# w6_hello.net
KiCad netlist of a schematic drawn in EAGLE
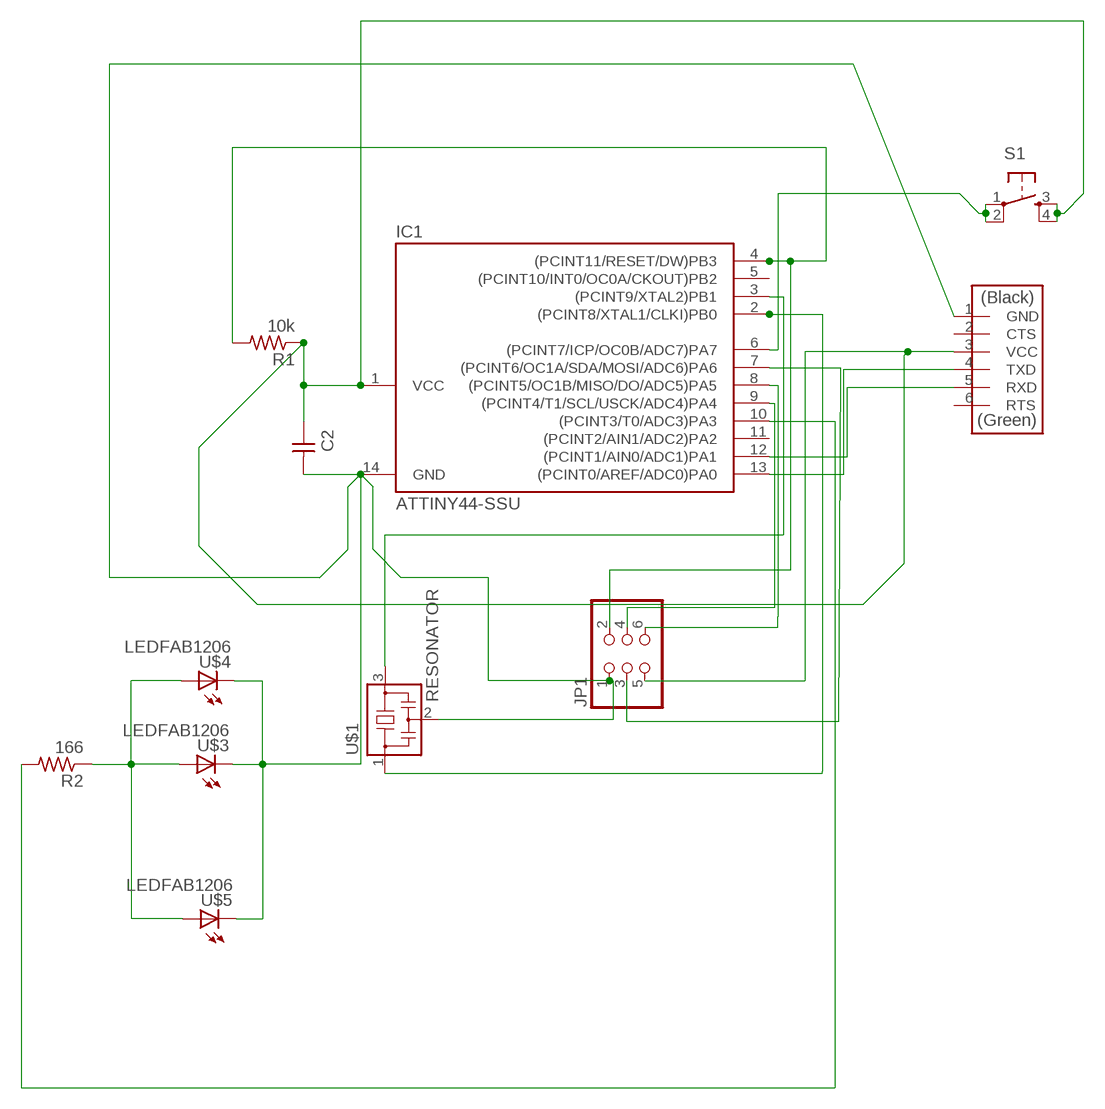
[diagram p0: schematic, sheet 1]

(export (version "E")
  (design (tool "Eeschema 10.0.6"))
  (components
    (comp (ref "C2")
      (value "CAP-UNPOLARIZEDFAB")
      (footprint "eagle-import:C1206FAB")
      (libsource (lib "eagle-import") (part "CAP-UNPOLARIZEDFAB"))
    )
    (comp (ref "IC1")
      (value "ATTINY44-SSU")
      (footprint "eagle-import:SOIC14")
      (libsource (lib "eagle-import") (part "ATTINY44-SSU"))
    )
    (comp (ref "JP1")
      (value "PINHD-2X3-SMD")
      (footprint "eagle-import:2X03SMD")
      (libsource (lib "eagle-import") (part "PINHD-2X3-SMD"))
    )
    (comp (ref "R1")
      (value "10k")
      (footprint "eagle-import:R1206")
      (libsource (lib "eagle-import") (part "RES-US1206"))
    )
    (comp (ref "R2")
      (value "166")
      (footprint "eagle-import:R1206")
      (libsource (lib "eagle-import") (part "RES-US1206"))
    )
    (comp (ref "S1")
      (value "6MM_SWITCH6MM_SWITCH")
      (footprint "eagle-import:6MM_SWITCH")
      (libsource (lib "eagle-import") (part "6MM_SWITCH6MM_SWITCH"))
    )
    (comp (ref "U$1")
      (value "RESONATOR")
      (footprint "eagle-import:EFOBM")
      (libsource (lib "eagle-import") (part "RESONATOR"))
    )
    (comp (ref "U$2")
      (value "FTDI-SMD-HEADER")
      (footprint "eagle-import:1X06SMD")
      (libsource (lib "eagle-import") (part "FTDI-SMD-HEADER"))
    )
    (comp (ref "U$3")
      (value "LEDFAB1206")
      (footprint "eagle-import:LED1206FAB")
      (libsource (lib "eagle-import") (part "LEDFAB1206"))
    )
    (comp (ref "U$4")
      (value "LEDFAB1206")
      (footprint "eagle-import:LED1206FAB")
      (libsource (lib "eagle-import") (part "LEDFAB1206"))
    )
    (comp (ref "U$5")
      (value "LEDFAB1206")
      (footprint "eagle-import:LED1206FAB")
      (libsource (lib "eagle-import") (part "LEDFAB1206"))
    )
  )
  (nets
    (net (code "1") (name "Net-(IC1-(PCINT0{slash}AREF{slash}ADC0)PA0)") (class "Default")
      (node (ref "IC1") (pin "13") (pinfunction "(PCINT0/AREF/ADC0)PA0_13") (pintype "bidirectional"))
      (node (ref "U$2") (pin "4") (pinfunction "TXD_4") (pintype "bidirectional"))
    )
    (net (code "2") (name "Net-(IC1-(PCINT1{slash}AIN0{slash}ADC1)PA1)") (class "Default")
      (node (ref "IC1") (pin "12") (pinfunction "(PCINT1/AIN0/ADC1)PA1_12") (pintype "bidirectional"))
      (node (ref "U$2") (pin "5") (pinfunction "RXD_5") (pintype "bidirectional"))
    )
    (net (code "3") (name "Net-(IC1-(PCINT3{slash}T0{slash}ADC3)PA3)") (class "Default")
      (node (ref "IC1") (pin "10") (pinfunction "(PCINT3/T0/ADC3)PA3_10") (pintype "bidirectional"))
      (node (ref "R2") (pin "2") (pinfunction "2_2") (pintype "passive"))
    )
    (net (code "4") (name "Net-(IC1-(PCINT4{slash}T1{slash}SCL{slash}USCK{slash}ADC4)PA4)") (class "Default")
      (node (ref "IC1") (pin "9") (pinfunction "(PCINT4/T1/SCL/USCK/ADC4)PA4_9") (pintype "bidirectional"))
      (node (ref "JP1") (pin "4") (pinfunction "4_4") (pintype "passive"))
    )
    (net (code "5") (name "Net-(IC1-(PCINT5{slash}OC1B{slash}MISO{slash}DO{slash}ADC5)PA5)") (class "Default")
      (node (ref "IC1") (pin "8") (pinfunction "(PCINT5/OC1B/MISO/DO/ADC5)PA5_8") (pintype "bidirectional"))
      (node (ref "JP1") (pin "6") (pinfunction "6_6") (pintype "passive"))
    )
    (net (code "6") (name "Net-(IC1-(PCINT6{slash}OC1A{slash}SDA{slash}MOSI{slash}ADC6)PA6)") (class "Default")
      (node (ref "IC1") (pin "7") (pinfunction "(PCINT6/OC1A/SDA/MOSI/ADC6)PA6_7") (pintype "bidirectional"))
      (node (ref "JP1") (pin "3") (pinfunction "3_3") (pintype "passive"))
    )
    (net (code "7") (name "Net-(IC1-(PCINT7{slash}ICP{slash}OC0B{slash}ADC7)PA7)") (class "Default")
      (node (ref "IC1") (pin "6") (pinfunction "(PCINT7/ICP/OC0B/ADC7)PA7_6") (pintype "bidirectional"))
      (node (ref "S1") (pin "1") (pinfunction "P_1") (pintype "passive"))
      (node (ref "S1") (pin "2") (pinfunction "P1_2") (pintype "passive"))
    )
    (net (code "8") (name "Net-(IC1-(PCINT8{slash}XTAL1{slash}CLKI)PB0)") (class "Default")
      (node (ref "IC1") (pin "2") (pinfunction "(PCINT8/XTAL1/CLKI)PB0_2") (pintype "bidirectional"))
      (node (ref "U$1") (pin "1") (pinfunction "1_1") (pintype "passive"))
    )
    (net (code "9") (name "Net-(IC1-(PCINT9{slash}XTAL2)PB1)") (class "Default")
      (node (ref "IC1") (pin "3") (pinfunction "(PCINT9/XTAL2)PB1_3") (pintype "bidirectional"))
      (node (ref "U$1") (pin "3") (pinfunction "3_3") (pintype "passive"))
    )
    (net (code "10") (name "Net-(IC1-(PCINT11{slash}RESET{slash}DW)PB3)") (class "Default")
      (node (ref "IC1") (pin "4") (pinfunction "(PCINT11/RESET/DW)PB3_4") (pintype "bidirectional"))
      (node (ref "JP1") (pin "2") (pinfunction "2_2") (pintype "passive"))
      (node (ref "R1") (pin "2") (pinfunction "2_2") (pintype "passive"))
    )
    (net (code "11") (name "Net-(IC1-GND)") (class "Default")
      (node (ref "C2") (pin "2") (pinfunction "2_2") (pintype "passive"))
      (node (ref "IC1") (pin "14") (pinfunction "GND_14") (pintype "power_in"))
      (node (ref "JP1") (pin "1") (pinfunction "1_1") (pintype "passive"))
      (node (ref "U$1") (pin "2") (pinfunction "2_2") (pintype "passive"))
      (node (ref "U$2") (pin "1") (pinfunction "GND_1") (pintype "bidirectional"))
      (node (ref "U$3") (pin "2") (pinfunction "C_2") (pintype "passive"))
      (node (ref "U$4") (pin "2") (pinfunction "C_2") (pintype "passive"))
      (node (ref "U$5") (pin "2") (pinfunction "C_2") (pintype "passive"))
    )
    (net (code "12") (name "Net-(IC1-VCC)") (class "Default")
      (node (ref "C2") (pin "1") (pinfunction "1_1") (pintype "passive"))
      (node (ref "IC1") (pin "1") (pinfunction "VCC_1") (pintype "power_in"))
      (node (ref "JP1") (pin "5") (pinfunction "5_5") (pintype "passive"))
      (node (ref "R1") (pin "1") (pinfunction "1_1") (pintype "passive"))
      (node (ref "S1") (pin "3") (pinfunction "S_3") (pintype "passive"))
      (node (ref "S1") (pin "4") (pinfunction "S1_4") (pintype "passive"))
      (node (ref "U$2") (pin "3") (pinfunction "VCC_3") (pintype "bidirectional"))
    )
    (net (code "13") (name "Net-(U$3-A)") (class "Default")
      (node (ref "R2") (pin "1") (pinfunction "1_1") (pintype "passive"))
      (node (ref "U$3") (pin "1") (pinfunction "A_1") (pintype "passive"))
      (node (ref "U$4") (pin "1") (pinfunction "A_1") (pintype "passive"))
      (node (ref "U$5") (pin "1") (pinfunction "A_1") (pintype "passive"))
    )
    (net (code "14") (name "unconnected-(IC1-(PCINT2{slash}AIN1{slash}ADC2)PA2-Pad11)") (class "Default")
      (node (ref "IC1") (pin "11") (pinfunction "(PCINT2/AIN1/ADC2)PA2_11") (pintype "bidirectional"))
    )
    (net (code "15") (name "unconnected-(IC1-(PCINT10{slash}INT0{slash}OC0A{slash}CKOUT)PB2-Pad5)") (class "Default")
      (node (ref "IC1") (pin "5") (pinfunction "(PCINT10/INT0/OC0A/CKOUT)PB2_5") (pintype "bidirectional"))
    )
    (net (code "16") (name "unconnected-(U$2-CTS-Pad2)") (class "Default")
      (node (ref "U$2") (pin "2") (pinfunction "CTS_2") (pintype "bidirectional"))
    )
    (net (code "17") (name "unconnected-(U$2-RTS-Pad6)") (class "Default")
      (node (ref "U$2") (pin "6") (pinfunction "RTS_6") (pintype "bidirectional"))
    )
  )
)
